# ArtFire.net
KiCad netlist of a schematic drawn in Altium Designer
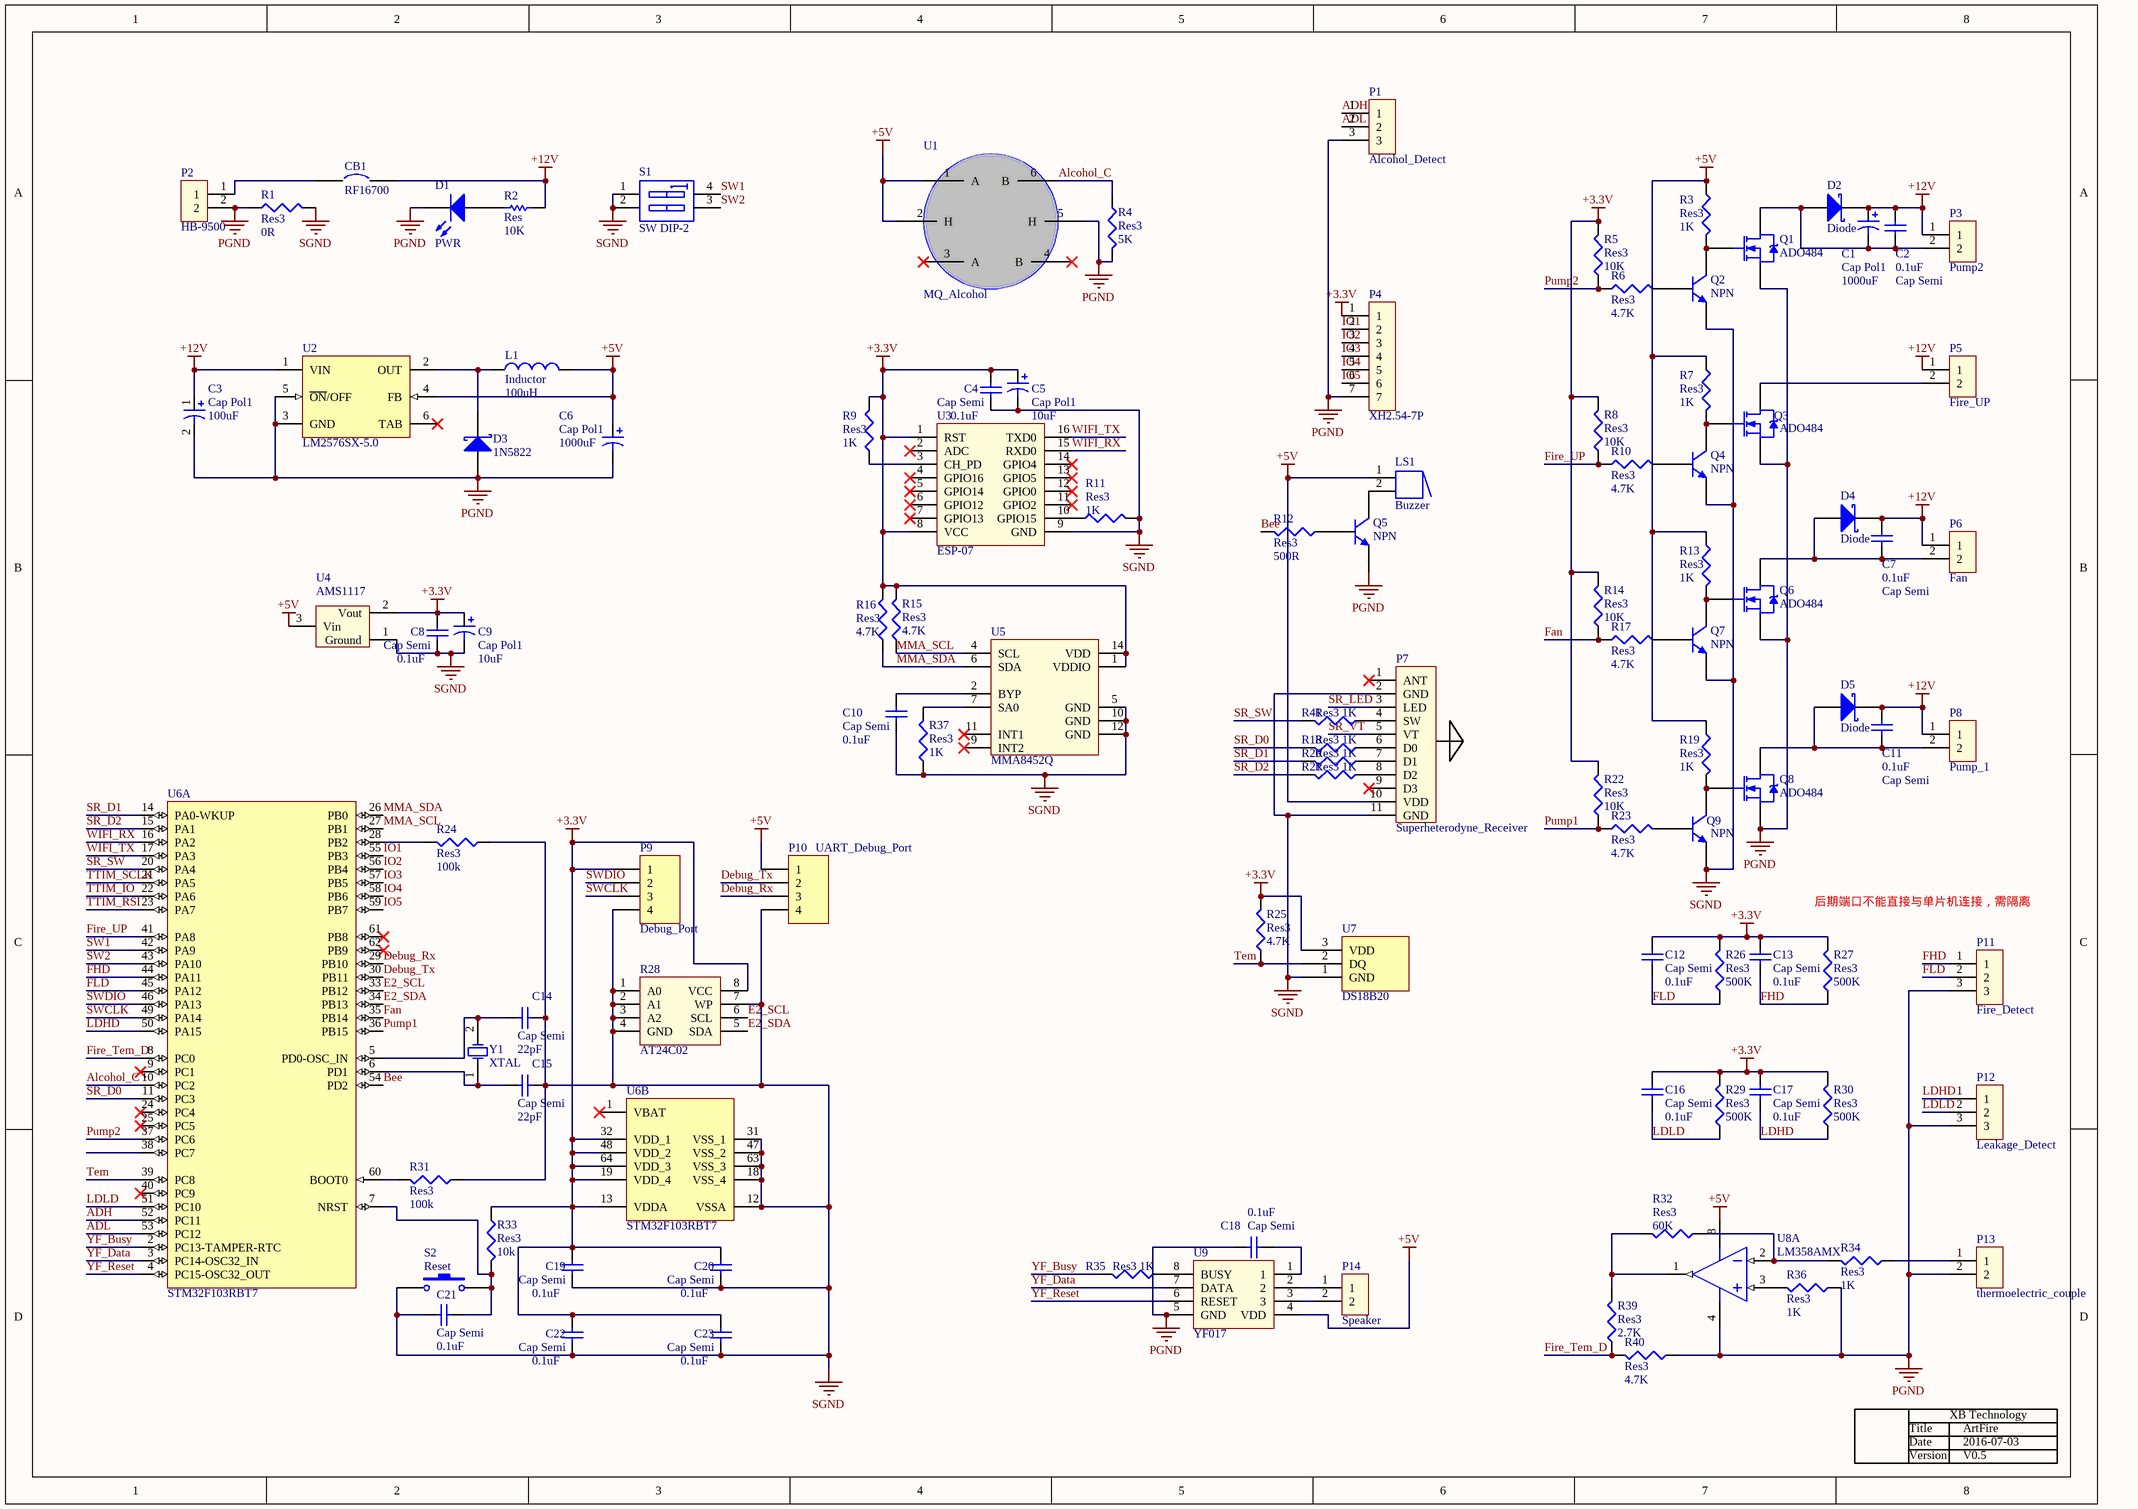
[diagram p0: ArtFire.SchDoc]

(export (version "E")
  (design (tool "Eeschema 10.0.6"))
  (components
    (comp (ref "C1")
      (value "Cap Pol1")
      (footprint "CAP_10*10MM")
      (description "Polarized Capacitor (Radial)")
      (fields (field (name "ALTIUM_VALUE") "1000uF"))
      (libsource (lib "Miscellaneous Devices") (part "Cap Pol1"))
    )
    (comp (ref "C2")
      (value "Cap Semi")
      (footprint "6-0805_N")
      (description "Capacitor (Semiconductor SIM Model)")
      (fields (field (name "ALTIUM_VALUE") "0.1uF"))
      (libsource (lib "Miscellaneous Devices") (part "Cap Semi"))
    )
    (comp (ref "C3")
      (value "Cap Pol1")
      (footprint "6032")
      (description "Polarized Capacitor (Radial)")
      (fields (field (name "ALTIUM_VALUE") "100uF"))
      (libsource (lib "") (part "Cap Pol1_1"))
    )
    (comp (ref "C4")
      (value "Cap Semi")
      (footprint "6-0805_N")
      (description "Capacitor (Semiconductor SIM Model)")
      (fields (field (name "ALTIUM_VALUE") "0.1uF"))
      (libsource (lib "Miscellaneous Devices") (part "Cap Semi"))
    )
    (comp (ref "C5")
      (value "Cap Pol1")
      (footprint "Cap_5*4mm")
      (description "Polarized Capacitor (Radial)")
      (fields (field (name "ALTIUM_VALUE") "10uF"))
      (libsource (lib "Miscellaneous Devices") (part "Cap Pol1"))
    )
    (comp (ref "C6")
      (value "Cap Pol1")
      (footprint "CAP_10*10MM")
      (description "Polarized Capacitor (Radial)")
      (fields (field (name "ALTIUM_VALUE") "1000uF"))
      (libsource (lib "Miscellaneous Devices") (part "Cap Pol1"))
    )
    (comp (ref "C7")
      (value "Cap Semi")
      (footprint "6-0805_N")
      (description "Capacitor (Semiconductor SIM Model)")
      (fields (field (name "ALTIUM_VALUE") "0.1uF"))
      (libsource (lib "Miscellaneous Devices") (part "Cap Semi"))
    )
    (comp (ref "C8")
      (value "Cap Semi")
      (footprint "6-0805_N")
      (description "Capacitor (Semiconductor SIM Model)")
      (fields (field (name "ALTIUM_VALUE") "0.1uF"))
      (libsource (lib "Miscellaneous Devices") (part "Cap Semi"))
    )
    (comp (ref "C9")
      (value "Cap Pol1")
      (footprint "Cap_5*4mm")
      (description "Polarized Capacitor (Radial)")
      (fields (field (name "ALTIUM_VALUE") "10uF"))
      (libsource (lib "Miscellaneous Devices") (part "Cap Pol1"))
    )
    (comp (ref "C10")
      (value "Cap Semi")
      (footprint "6-0805_N")
      (description "Capacitor (Semiconductor SIM Model)")
      (fields (field (name "ALTIUM_VALUE") "0.1uF"))
      (libsource (lib "Miscellaneous Devices") (part "Cap Semi"))
    )
    (comp (ref "C11")
      (value "Cap Semi")
      (footprint "6-0805_N")
      (description "Capacitor (Semiconductor SIM Model)")
      (fields (field (name "ALTIUM_VALUE") "0.1uF"))
      (libsource (lib "Miscellaneous Devices") (part "Cap Semi"))
    )
    (comp (ref "C12")
      (value "Cap Semi")
      (footprint "6-0805_N")
      (description "Capacitor (Semiconductor SIM Model)")
      (fields (field (name "ALTIUM_VALUE") "0.1uF"))
      (libsource (lib "Miscellaneous Devices") (part "Cap Semi"))
    )
    (comp (ref "C13")
      (value "Cap Semi")
      (footprint "6-0805_N")
      (description "Capacitor (Semiconductor SIM Model)")
      (fields (field (name "ALTIUM_VALUE") "0.1uF"))
      (libsource (lib "Miscellaneous Devices") (part "Cap Semi"))
    )
    (comp (ref "C14")
      (value "Cap Semi")
      (footprint "6-0805_N")
      (description "Capacitor (Semiconductor SIM Model)")
      (fields (field (name "ALTIUM_VALUE") "22pF"))
      (libsource (lib "Miscellaneous Devices") (part "Cap Semi"))
    )
    (comp (ref "C15")
      (value "Cap Semi")
      (footprint "6-0805_N")
      (description "Capacitor (Semiconductor SIM Model)")
      (fields (field (name "ALTIUM_VALUE") "22pF"))
      (libsource (lib "Miscellaneous Devices") (part "Cap Semi"))
    )
    (comp (ref "C16")
      (value "Cap Semi")
      (footprint "6-0805_N")
      (description "Capacitor (Semiconductor SIM Model)")
      (fields (field (name "ALTIUM_VALUE") "0.1uF"))
      (libsource (lib "Miscellaneous Devices") (part "Cap Semi"))
    )
    (comp (ref "C17")
      (value "Cap Semi")
      (footprint "6-0805_N")
      (description "Capacitor (Semiconductor SIM Model)")
      (fields (field (name "ALTIUM_VALUE") "0.1uF"))
      (libsource (lib "Miscellaneous Devices") (part "Cap Semi"))
    )
    (comp (ref "C18")
      (value "Cap Semi")
      (footprint "6-0805_N")
      (description "Capacitor (Semiconductor SIM Model)")
      (fields (field (name "ALTIUM_VALUE") "0.1uF"))
      (libsource (lib "Miscellaneous Devices") (part "Cap Semi"))
    )
    (comp (ref "C19")
      (value "Cap Semi")
      (footprint "6-0805_N")
      (description "Capacitor (Semiconductor SIM Model)")
      (fields (field (name "ALTIUM_VALUE") "0.1uF"))
      (libsource (lib "Miscellaneous Devices") (part "Cap Semi"))
    )
    (comp (ref "C20")
      (value "Cap Semi")
      (footprint "6-0805_N")
      (description "Capacitor (Semiconductor SIM Model)")
      (fields (field (name "ALTIUM_VALUE") "0.1uF"))
      (libsource (lib "Miscellaneous Devices") (part "Cap Semi"))
    )
    (comp (ref "C21")
      (value "Cap Semi")
      (footprint "6-0805_N")
      (description "Capacitor (Semiconductor SIM Model)")
      (fields (field (name "ALTIUM_VALUE") "0.1uF"))
      (libsource (lib "Miscellaneous Devices") (part "Cap Semi"))
    )
    (comp (ref "C22")
      (value "Cap Semi")
      (footprint "6-0805_N")
      (description "Capacitor (Semiconductor SIM Model)")
      (fields (field (name "ALTIUM_VALUE") "0.1uF"))
      (libsource (lib "Miscellaneous Devices") (part "Cap Semi"))
    )
    (comp (ref "C23")
      (value "Cap Semi")
      (footprint "6-0805_N")
      (description "Capacitor (Semiconductor SIM Model)")
      (fields (field (name "ALTIUM_VALUE") "0.1uF"))
      (libsource (lib "Miscellaneous Devices") (part "Cap Semi"))
    )
    (comp (ref "CB1")
      (value "RF16700")
      (footprint "SPST-2")
      (description "Circuit Breaker")
      (libsource (lib "Miscellaneous Devices") (part "Circuit Breaker"))
    )
    (comp (ref "D1")
      (value "PWR")
      (footprint "6-0805_N")
      (description "Typical INFRARED GaAs LED")
      (libsource (lib "Miscellaneous Devices") (part "LED0"))
    )
    (comp (ref "D2")
      (value "Diode")
      (footprint "US1M")
      (description "Silicon RF Schottky Diode for Mixer Applications in the VHF/UHF Range")
      (libsource (lib "Miscellaneous Devices") (part "Diode BAT17"))
    )
    (comp (ref "D3")
      (value "1N5822")
      (footprint "US1M")
      (description "Silicon RF Schottky Diode for Mixer Applications in the VHF/UHF Range")
      (libsource (lib "Miscellaneous Devices") (part "Diode BAT17"))
    )
    (comp (ref "D4")
      (value "Diode")
      (footprint "US1M")
      (description "Silicon RF Schottky Diode for Mixer Applications in the VHF/UHF Range")
      (libsource (lib "Miscellaneous Devices") (part "Diode BAT17"))
    )
    (comp (ref "D5")
      (value "Diode")
      (footprint "US1M")
      (description "Silicon RF Schottky Diode for Mixer Applications in the VHF/UHF Range")
      (libsource (lib "Miscellaneous Devices") (part "Diode BAT17"))
    )
    (comp (ref "L1")
      (value "Inductor")
      (footprint "CDRH127")
      (fields (field (name "ALTIUM_VALUE") "100uH"))
      (libsource (lib "Miscellaneous Devices") (part "Inductor"))
    )
    (comp (ref "LS1")
      (value "Buzzer")
      (footprint "BUZZER")
      (description "Magnetic Transducer Buzzer")
      (libsource (lib "Miscellaneous Devices") (part "Buzzer"))
    )
    (comp (ref "P1")
      (value "Alcohol_Detect")
      (footprint "XH2.54-3P")
      (libsource (lib "XH2.54") (part "XH2.54-3P"))
    )
    (comp (ref "P2")
      (value "HB-9500")
      (footprint "HB-9500")
      (description "High current connector")
      (libsource (lib "Simon'Library") (part "HB-9500"))
    )
    (comp (ref "P3") (value "Pump2") (footprint "CH3.96_2P") (libsource (lib "CH3.96") (part "CH3.96_2P")))
    (comp (ref "P4")
      (value "XH2.54-7P")
      (footprint "XH2.54-7P")
      (libsource (lib "XH2.54") (part "XH2.54-7P"))
    )
    (comp (ref "P5") (value "Fire_UP") (footprint "KF3.96_2P") (libsource (lib "KF3.96") (part "KF3.96")))
    (comp (ref "P6") (value "Fan") (footprint "XH2.54-2P") (libsource (lib "XH2.54") (part "XH2.54-2P")))
    (comp (ref "P7")
      (value "Superheterodyne_Receiver")
      (footprint "Sperheterodyne_Receiver")
      (libsource (lib "Simon'Library") (part "Superheterodyne_Receiver"))
    )
    (comp (ref "P8") (value "Pump_1") (footprint "CH3.96_2P") (libsource (lib "CH3.96") (part "CH3.96_2P")))
    (comp (ref "P9")
      (value "Debug_Port")
      (footprint "HDR1X4")
      (description "Header, 4-Pin")
      (libsource (lib "Miscellaneous Connectors") (part "Header 4"))
    )
    (comp (ref "P10")
      (value "UART_Debug_Port")
      (footprint "HDR1X4")
      (description "Header, 4-Pin")
      (libsource (lib "Miscellaneous Connectors") (part "Header 4"))
    )
    (comp (ref "P11")
      (value "Fire_Detect")
      (footprint "CH3.96_3P")
      (libsource (lib "CH3.96") (part "CH3.96_3P"))
    )
    (comp (ref "P12")
      (value "Leakage_Detect")
      (footprint "XH2.54-3P")
      (libsource (lib "XH2.54") (part "XH2.54-3P"))
    )
    (comp (ref "P13")
      (value "thermoelectric_couple")
      (footprint "KF7.62-2P")
      (libsource (lib "KF3.96") (part "KF3.96"))
    )
    (comp (ref "P14") (value "Speaker") (footprint "XH2.54-2P") (libsource (lib "XH2.54") (part "XH2.54-2P")))
    (comp (ref "Q1")
      (value "ADO484")
      (footprint "DPAK_AOD484")
      (description "N-Channel Power MOSFET")
      (libsource (lib "Miscellaneous Devices") (part "NMOS-2"))
    )
    (comp (ref "Q2")
      (value "NPN")
      (footprint "SOT-23_N")
      (description "NPN Bipolar Transistor")
      (libsource (lib "Miscellaneous Devices") (part "NPN"))
    )
    (comp (ref "Q3")
      (value "ADO484")
      (footprint "DPAK_AOD484")
      (description "N-Channel Power MOSFET")
      (libsource (lib "Miscellaneous Devices") (part "NMOS-2"))
    )
    (comp (ref "Q4")
      (value "NPN")
      (footprint "SOT-23_N")
      (description "NPN Bipolar Transistor")
      (libsource (lib "Miscellaneous Devices") (part "NPN"))
    )
    (comp (ref "Q5")
      (value "NPN")
      (footprint "SOT-23_N")
      (description "NPN Bipolar Transistor")
      (libsource (lib "Miscellaneous Devices") (part "NPN"))
    )
    (comp (ref "Q6")
      (value "ADO484")
      (footprint "DPAK_AOD484")
      (description "N-Channel Power MOSFET")
      (libsource (lib "Miscellaneous Devices") (part "NMOS-2"))
    )
    (comp (ref "Q7")
      (value "NPN")
      (footprint "SOT-23_N")
      (description "NPN Bipolar Transistor")
      (libsource (lib "Miscellaneous Devices") (part "NPN"))
    )
    (comp (ref "Q8")
      (value "ADO484")
      (footprint "DPAK_AOD484")
      (description "N-Channel Power MOSFET")
      (libsource (lib "Miscellaneous Devices") (part "NMOS-2"))
    )
    (comp (ref "Q9")
      (value "NPN")
      (footprint "SOT-23_N")
      (description "NPN Bipolar Transistor")
      (libsource (lib "Miscellaneous Devices") (part "NPN"))
    )
    (comp (ref "R1")
      (value "Res3")
      (footprint "6-0805_N")
      (description "Resistor")
      (fields (field (name "ALTIUM_VALUE") "0R"))
      (libsource (lib "Miscellaneous Devices") (part "Res3"))
    )
    (comp (ref "R2")
      (value "Res")
      (footprint "6-0805_N")
      (description "Resistor")
      (fields (field (name "ALTIUM_VALUE") "10K"))
      (libsource (lib "Miscellaneous Devices") (part "Res1"))
    )
    (comp (ref "R3")
      (value "Res3")
      (footprint "6-0805_N")
      (description "Resistor")
      (fields (field (name "ALTIUM_VALUE") "1K"))
      (libsource (lib "Miscellaneous Devices") (part "Res3"))
    )
    (comp (ref "R4")
      (value "Res3")
      (footprint "6-0805_N")
      (description "Resistor")
      (fields (field (name "ALTIUM_VALUE") "5K"))
      (libsource (lib "Miscellaneous Devices") (part "Res3"))
    )
    (comp (ref "R5")
      (value "Res3")
      (footprint "6-0805_N")
      (description "Resistor")
      (fields (field (name "ALTIUM_VALUE") "10K"))
      (libsource (lib "Miscellaneous Devices") (part "Res3"))
    )
    (comp (ref "R6")
      (value "Res3")
      (footprint "6-0805_N")
      (description "Resistor")
      (fields (field (name "ALTIUM_VALUE") "4.7K"))
      (libsource (lib "Miscellaneous Devices") (part "Res3"))
    )
    (comp (ref "R7")
      (value "Res3")
      (footprint "6-0805_N")
      (description "Resistor")
      (fields (field (name "ALTIUM_VALUE") "1K"))
      (libsource (lib "Miscellaneous Devices") (part "Res3"))
    )
    (comp (ref "R8")
      (value "Res3")
      (footprint "6-0805_N")
      (description "Resistor")
      (fields (field (name "ALTIUM_VALUE") "10K"))
      (libsource (lib "Miscellaneous Devices") (part "Res3"))
    )
    (comp (ref "R9")
      (value "Res3")
      (footprint "6-0805_N")
      (description "Resistor")
      (fields (field (name "ALTIUM_VALUE") "1K"))
      (libsource (lib "Miscellaneous Devices") (part "Res3"))
    )
    (comp (ref "R10")
      (value "Res3")
      (footprint "6-0805_N")
      (description "Resistor")
      (fields (field (name "ALTIUM_VALUE") "4.7K"))
      (libsource (lib "Miscellaneous Devices") (part "Res3"))
    )
    (comp (ref "R11")
      (value "Res3")
      (footprint "6-0805_N")
      (description "Resistor")
      (fields (field (name "ALTIUM_VALUE") "1K"))
      (libsource (lib "Miscellaneous Devices") (part "Res3"))
    )
    (comp (ref "R12")
      (value "Res3")
      (footprint "6-0805_N")
      (description "Resistor")
      (fields (field (name "ALTIUM_VALUE") "500R"))
      (libsource (lib "Miscellaneous Devices") (part "Res3"))
    )
    (comp (ref "R13")
      (value "Res3")
      (footprint "6-0805_N")
      (description "Resistor")
      (fields (field (name "ALTIUM_VALUE") "1K"))
      (libsource (lib "Miscellaneous Devices") (part "Res3"))
    )
    (comp (ref "R14")
      (value "Res3")
      (footprint "6-0805_N")
      (description "Resistor")
      (fields (field (name "ALTIUM_VALUE") "10K"))
      (libsource (lib "Miscellaneous Devices") (part "Res3"))
    )
    (comp (ref "R15")
      (value "Res3")
      (footprint "6-0805_N")
      (description "Resistor")
      (fields (field (name "ALTIUM_VALUE") "4.7K"))
      (libsource (lib "Miscellaneous Devices") (part "Res3"))
    )
    (comp (ref "R16")
      (value "Res3")
      (footprint "6-0805_N")
      (description "Resistor")
      (fields (field (name "ALTIUM_VALUE") "4.7K"))
      (libsource (lib "Miscellaneous Devices") (part "Res3"))
    )
    (comp (ref "R17")
      (value "Res3")
      (footprint "6-0805_N")
      (description "Resistor")
      (fields (field (name "ALTIUM_VALUE") "4.7K"))
      (libsource (lib "Miscellaneous Devices") (part "Res3"))
    )
    (comp (ref "R18")
      (value "Res3")
      (footprint "6-0805_N")
      (description "Resistor")
      (fields (field (name "ALTIUM_VALUE") "1K"))
      (libsource (lib "Miscellaneous Devices") (part "Res3"))
    )
    (comp (ref "R19")
      (value "Res3")
      (footprint "6-0805_N")
      (description "Resistor")
      (fields (field (name "ALTIUM_VALUE") "1K"))
      (libsource (lib "Miscellaneous Devices") (part "Res3"))
    )
    (comp (ref "R20")
      (value "Res3")
      (footprint "6-0805_N")
      (description "Resistor")
      (fields (field (name "ALTIUM_VALUE") "1K"))
      (libsource (lib "Miscellaneous Devices") (part "Res3"))
    )
    (comp (ref "R21")
      (value "Res3")
      (footprint "6-0805_N")
      (description "Resistor")
      (fields (field (name "ALTIUM_VALUE") "1K"))
      (libsource (lib "Miscellaneous Devices") (part "Res3"))
    )
    (comp (ref "R22")
      (value "Res3")
      (footprint "6-0805_N")
      (description "Resistor")
      (fields (field (name "ALTIUM_VALUE") "10K"))
      (libsource (lib "Miscellaneous Devices") (part "Res3"))
    )
    (comp (ref "R23")
      (value "Res3")
      (footprint "6-0805_N")
      (description "Resistor")
      (fields (field (name "ALTIUM_VALUE") "4.7K"))
      (libsource (lib "Miscellaneous Devices") (part "Res3"))
    )
    (comp (ref "R24")
      (value "Res3")
      (footprint "6-0805_N")
      (description "Resistor")
      (fields (field (name "ALTIUM_VALUE") "100k"))
      (libsource (lib "Miscellaneous Devices") (part "Res3"))
    )
    (comp (ref "R25")
      (value "Res3")
      (footprint "6-0805_N")
      (description "Resistor")
      (fields (field (name "ALTIUM_VALUE") "4.7K"))
      (libsource (lib "Miscellaneous Devices") (part "Res3"))
    )
    (comp (ref "R26")
      (value "Res3")
      (footprint "6-0805_N")
      (description "Resistor")
      (fields (field (name "ALTIUM_VALUE") "500K"))
      (libsource (lib "Miscellaneous Devices") (part "Res3"))
    )
    (comp (ref "R27")
      (value "Res3")
      (footprint "6-0805_N")
      (description "Resistor")
      (fields (field (name "ALTIUM_VALUE") "500K"))
      (libsource (lib "Miscellaneous Devices") (part "Res3"))
    )
    (comp (ref "R28")
      (value "AT24C02")
      (footprint "SOP8_TDA2822")
      (libsource (lib "Simon'Library") (part "AT24C02"))
    )
    (comp (ref "R29")
      (value "Res3")
      (footprint "6-0805_N")
      (description "Resistor")
      (fields (field (name "ALTIUM_VALUE") "500K"))
      (libsource (lib "Miscellaneous Devices") (part "Res3"))
    )
    (comp (ref "R30")
      (value "Res3")
      (footprint "6-0805_N")
      (description "Resistor")
      (fields (field (name "ALTIUM_VALUE") "500K"))
      (libsource (lib "Miscellaneous Devices") (part "Res3"))
    )
    (comp (ref "R31")
      (value "Res3")
      (footprint "6-0805_N")
      (description "Resistor")
      (fields (field (name "ALTIUM_VALUE") "100k"))
      (libsource (lib "Miscellaneous Devices") (part "Res3"))
    )
    (comp (ref "R32")
      (value "Res3")
      (footprint "6-0805_N")
      (description "Resistor")
      (fields (field (name "ALTIUM_VALUE") "60K"))
      (libsource (lib "Miscellaneous Devices") (part "Res3"))
    )
    (comp (ref "R33")
      (value "Res3")
      (footprint "6-0805_N")
      (description "Resistor")
      (fields (field (name "ALTIUM_VALUE") "10k"))
      (libsource (lib "Miscellaneous Devices") (part "Res3"))
    )
    (comp (ref "R34")
      (value "Res3")
      (footprint "6-0805_N")
      (description "Resistor")
      (fields (field (name "ALTIUM_VALUE") "1K"))
      (libsource (lib "Miscellaneous Devices") (part "Res3"))
    )
    (comp (ref "R35")
      (value "Res3")
      (footprint "6-0805_N")
      (description "Resistor")
      (fields (field (name "ALTIUM_VALUE") "1K"))
      (libsource (lib "Miscellaneous Devices") (part "Res3"))
    )
    (comp (ref "R36")
      (value "Res3")
      (footprint "6-0805_N")
      (description "Resistor")
      (fields (field (name "ALTIUM_VALUE") "1K"))
      (libsource (lib "Miscellaneous Devices") (part "Res3"))
    )
    (comp (ref "R37")
      (value "Res3")
      (footprint "6-0805_N")
      (description "Resistor")
      (fields (field (name "ALTIUM_VALUE") "1K"))
      (libsource (lib "Miscellaneous Devices") (part "Res3"))
    )
    (comp (ref "R39")
      (value "Res3")
      (footprint "6-0805_N")
      (description "Resistor")
      (fields (field (name "ALTIUM_VALUE") "2.7K"))
      (libsource (lib "Miscellaneous Devices") (part "Res3"))
    )
    (comp (ref "R40")
      (value "Res3")
      (footprint "6-0805_N")
      (description "Resistor")
      (fields (field (name "ALTIUM_VALUE") "4.7K"))
      (libsource (lib "Miscellaneous Devices") (part "Res3"))
    )
    (comp (ref "R41")
      (value "Res3")
      (footprint "6-0805_N")
      (description "Resistor")
      (fields (field (name "ALTIUM_VALUE") "1K"))
      (libsource (lib "Miscellaneous Devices") (part "Res3"))
    )
    (comp (ref "S1")
      (value "SW DIP-2")
      (footprint "DIP-4")
      (description "DIP Switch, 2 Position, SPST")
      (libsource (lib "Miscellaneous Devices") (part "SW DIP-2"))
    )
    (comp (ref "S2")
      (value "Reset")
      (footprint "SWP_PB_6.5mm")
      (description "Switch")
      (libsource (lib "Miscellaneous Devices") (part "SW-PB"))
    )
    (comp (ref "U1") (value "MQ_Alcohol") (footprint "MQ") (libsource (lib "Simon'Library") (part "MQ")))
    (comp (ref "U2")
      (value "LM2576SX-5.0")
      (footprint "TS5B_L")
      (description "SIMPLE SWITCHER® 3A Step-Down Voltage Regulator, 5-pin TO-263")
      (fields (field (name "MANUFACTURER") "National Semiconductor"))
      (libsource (lib "Altium Content Vault") (part "PM-REG-LM2575HVS-12"))
    )
    (comp (ref "U3")
      (value "ESP-07")
      (footprint "ESP-07_Wifi")
      (libsource (lib "Simon'Library") (part "ESP-07_Wifi"))
    )
    (comp (ref "U4")
      (value "AMS1117")
      (footprint "SOT223_N")
      (libsource (lib "Simon'Library") (part "AMS1117"))
    )
    (comp (ref "U5")
      (value "MMA8452Q")
      (footprint "QFN-16")
      (libsource (lib "Simon'Library") (part "MMA8452Q"))
    )
    (comp (ref "U6")
      (value "STM32F103RBT7")
      (footprint "LQFP64_L")
      (libsource (lib "Altium Content Vault") (part "MC-ARM-STM32F101-SQ64"))
    )
    (comp (ref "U7")
      (value "DS18B20")
      (footprint "TO-92A")
      (libsource (lib "Simon'Library") (part "DS18B20"))
    )
    (comp (ref "U8")
      (value "LM358AMX")
      (footprint "M08A_M")
      (description "Low Power Dual Operational Amplifier, 8-pin Narrow SOIC")
      (fields (field (name "MANUFACTURER") "National Semiconductor"))
      (libsource (lib "Altium Content Vault") (part "AMP-OPA-LM158-8"))
    )
    (comp (ref "U9") (value "YF017") (footprint "DIP-8") (libsource (lib "Simon'Library") (part "YF017")))
    (comp (ref "Y1")
      (value "XTAL")
      (footprint "XTAL")
      (description "Crystal Oscillator")
      (libsource (lib "Miscellaneous Devices") (part "XTAL"))
    )
  )
  (nets
    (net (code "1") (name "+3.3V") (class "Default")
      (node (ref "C12") (pin "2") (pinfunction "2_2") (pintype "passive"))
      (node (ref "C13") (pin "2") (pinfunction "2_2") (pintype "passive"))
      (node (ref "C16") (pin "2") (pinfunction "2_2") (pintype "passive"))
      (node (ref "C17") (pin "2") (pinfunction "2_2") (pintype "passive"))
      (node (ref "C19") (pin "1") (pinfunction "1_1") (pintype "passive"))
      (node (ref "C20") (pin "1") (pinfunction "1_1") (pintype "passive"))
      (node (ref "C22") (pin "1") (pinfunction "1_1") (pintype "passive"))
      (node (ref "C23") (pin "1") (pinfunction "1_1") (pintype "passive"))
      (node (ref "C4") (pin "1") (pinfunction "1_1") (pintype "passive"))
      (node (ref "C5") (pin "1") (pinfunction "1_1") (pintype "passive"))
      (node (ref "C8") (pin "1") (pinfunction "1_1") (pintype "passive"))
      (node (ref "C9") (pin "1") (pinfunction "1_1") (pintype "passive"))
      (node (ref "P4") (pin "1") (pinfunction "1_1") (pintype "passive"))
      (node (ref "P9") (pin "1") (pinfunction "1_1") (pintype "passive"))
      (node (ref "R14") (pin "2") (pinfunction "2_2") (pintype "passive"))
      (node (ref "R15") (pin "2") (pinfunction "2_2") (pintype "passive"))
      (node (ref "R16") (pin "2") (pinfunction "2_2") (pintype "passive"))
      (node (ref "R22") (pin "2") (pinfunction "2_2") (pintype "passive"))
      (node (ref "R25") (pin "2") (pinfunction "2_2") (pintype "passive"))
      (node (ref "R26") (pin "2") (pinfunction "2_2") (pintype "passive"))
      (node (ref "R27") (pin "2") (pinfunction "2_2") (pintype "passive"))
      (node (ref "R28") (pin "8") (pinfunction "VCC_8") (pintype "passive"))
      (node (ref "R29") (pin "2") (pinfunction "2_2") (pintype "passive"))
      (node (ref "R30") (pin "2") (pinfunction "2_2") (pintype "passive"))
      (node (ref "R33") (pin "1") (pinfunction "1_1") (pintype "passive"))
      (node (ref "R5") (pin "2") (pinfunction "2_2") (pintype "passive"))
      (node (ref "R8") (pin "2") (pinfunction "2_2") (pintype "passive"))
      (node (ref "R9") (pin "2") (pinfunction "2_2") (pintype "passive"))
      (node (ref "U3") (pin "1") (pinfunction "RST_1") (pintype "passive"))
      (node (ref "U3") (pin "8") (pinfunction "VCC_8") (pintype "passive"))
      (node (ref "U4") (pin "2") (pinfunction "Vout_2") (pintype "passive"))
      (node (ref "U5") (pin "1") (pinfunction "VDDIO_1") (pintype "passive"))
      (node (ref "U5") (pin "14") (pinfunction "VDD_14") (pintype "passive"))
      (node (ref "U6") (pin "13") (pinfunction "VDDA_13") (pintype "power_in"))
      (node (ref "U6") (pin "19") (pinfunction "VDD_4_19") (pintype "power_in"))
      (node (ref "U6") (pin "32") (pinfunction "VDD_1_32") (pintype "power_in"))
      (node (ref "U6") (pin "48") (pinfunction "VDD_2_48") (pintype "power_in"))
      (node (ref "U6") (pin "64") (pinfunction "VDD_3_64") (pintype "power_in"))
      (node (ref "U7") (pin "3") (pinfunction "VDD_3") (pintype "passive"))
    )
    (net (code "2") (name "+5V") (class "Default")
      (node (ref "C6") (pin "1") (pinfunction "1_1") (pintype "passive"))
      (node (ref "L1") (pin "2") (pinfunction "2_2") (pintype "passive"))
      (node (ref "LS1") (pin "1") (pinfunction "1_1") (pintype "passive"))
      (node (ref "P10") (pin "1") (pinfunction "1_1") (pintype "passive"))
      (node (ref "P7") (pin "10") (pinfunction "VDD_10") (pintype "passive"))
      (node (ref "R13") (pin "1") (pinfunction "1_1") (pintype "passive"))
      (node (ref "R19") (pin "1") (pinfunction "1_1") (pintype "passive"))
      (node (ref "R3") (pin "1") (pinfunction "1_1") (pintype "passive"))
      (node (ref "R7") (pin "1") (pinfunction "1_1") (pintype "passive"))
      (node (ref "U1") (pin "1") (pinfunction "A_1") (pintype "passive"))
      (node (ref "U1") (pin "2") (pinfunction "H_2") (pintype "passive"))
      (node (ref "U2") (pin "4") (pinfunction "FB_4") (pintype "input"))
      (node (ref "U4") (pin "3") (pinfunction "Vin_3") (pintype "passive"))
      (node (ref "U8") (pin "8") (pinfunction "V+_8") (pintype "power_in"))
      (node (ref "U9") (pin "4") (pinfunction "VDD_4") (pintype "passive"))
    )
    (net (code "3") (name "+12V") (class "Default")
      (node (ref "C1") (pin "1") (pinfunction "1_1") (pintype "passive"))
      (node (ref "C11") (pin "1") (pinfunction "1_1") (pintype "passive"))
      (node (ref "C2") (pin "1") (pinfunction "1_1") (pintype "passive"))
      (node (ref "C3") (pin "1") (pinfunction "1_1") (pintype "passive"))
      (node (ref "C7") (pin "1") (pinfunction "1_1") (pintype "passive"))
      (node (ref "CB1") (pin "2") (pinfunction "2_2") (pintype "passive"))
      (node (ref "D2") (pin "2") (pinfunction "K_2") (pintype "passive"))
      (node (ref "D4") (pin "2") (pinfunction "K_2") (pintype "passive"))
      (node (ref "D5") (pin "2") (pinfunction "K_2") (pintype "passive"))
      (node (ref "P3") (pin "1") (pinfunction "1_1") (pintype "passive"))
      (node (ref "P5") (pin "1") (pinfunction "1_1") (pintype "passive"))
      (node (ref "P6") (pin "1") (pinfunction "1_1") (pintype "passive"))
      (node (ref "P8") (pin "1") (pinfunction "1_1") (pintype "passive"))
      (node (ref "R2") (pin "2") (pinfunction "2_2") (pintype "passive"))
      (node (ref "U2") (pin "1") (pinfunction "VIN_1") (pintype "power_in"))
    )
    (net (code "4") (name "/ADH") (class "Default")
      (node (ref "P1") (pin "1") (pinfunction "1_1") (pintype "passive"))
      (node (ref "U6") (pin "52") (pinfunction "PC11_52") (pintype "bidirectional"))
    )
    (net (code "5") (name "/ADL") (class "Default")
      (node (ref "P1") (pin "2") (pinfunction "2_2") (pintype "passive"))
      (node (ref "U6") (pin "53") (pinfunction "PC12_53") (pintype "bidirectional"))
    )
    (net (code "6") (name "/Alcohol_C") (class "Default")
      (node (ref "R4") (pin "1") (pinfunction "1_1") (pintype "passive"))
      (node (ref "U1") (pin "6") (pinfunction "B_6") (pintype "passive"))
      (node (ref "U6") (pin "10") (pinfunction "PC2_10") (pintype "bidirectional"))
    )
    (net (code "7") (name "/Bee") (class "Default")
      (node (ref "R12") (pin "2") (pinfunction "2_2") (pintype "passive"))
      (node (ref "U6") (pin "54") (pinfunction "PD2_54") (pintype "bidirectional"))
    )
    (net (code "8") (name "/Debug_Rx") (class "Default")
      (node (ref "P10") (pin "3") (pinfunction "3_3") (pintype "passive"))
      (node (ref "U6") (pin "29") (pinfunction "PB10_29") (pintype "bidirectional"))
    )
    (net (code "9") (name "/Debug_Tx") (class "Default")
      (node (ref "P10") (pin "2") (pinfunction "2_2") (pintype "passive"))
      (node (ref "U6") (pin "30") (pinfunction "PB11_30") (pintype "bidirectional"))
    )
    (net (code "10") (name "/E2_SCL") (class "Default")
      (node (ref "R28") (pin "6") (pinfunction "SCL_6") (pintype "passive"))
      (node (ref "U6") (pin "33") (pinfunction "PB12_33") (pintype "bidirectional"))
    )
    (net (code "11") (name "/E2_SDA") (class "Default")
      (node (ref "R28") (pin "5") (pinfunction "SDA_5") (pintype "passive"))
      (node (ref "U6") (pin "34") (pinfunction "PB13_34") (pintype "bidirectional"))
    )
    (net (code "12") (name "/FHD") (class "Default")
      (node (ref "C13") (pin "1") (pinfunction "1_1") (pintype "passive"))
      (node (ref "P11") (pin "1") (pinfunction "1_1") (pintype "passive"))
      (node (ref "R27") (pin "1") (pinfunction "1_1") (pintype "passive"))
      (node (ref "U6") (pin "44") (pinfunction "PA11_44") (pintype "bidirectional"))
    )
    (net (code "13") (name "/FLD") (class "Default")
      (node (ref "C12") (pin "1") (pinfunction "1_1") (pintype "passive"))
      (node (ref "P11") (pin "2") (pinfunction "2_2") (pintype "passive"))
      (node (ref "R26") (pin "1") (pinfunction "1_1") (pintype "passive"))
      (node (ref "U6") (pin "45") (pinfunction "PA12_45") (pintype "bidirectional"))
    )
    (net (code "14") (name "/Fan") (class "Default")
      (node (ref "R14") (pin "1") (pinfunction "1_1") (pintype "passive"))
      (node (ref "R17") (pin "1") (pinfunction "1_1") (pintype "passive"))
      (node (ref "U6") (pin "35") (pinfunction "PB14_35") (pintype "bidirectional"))
    )
    (net (code "15") (name "/Fire_Tem_D") (class "Default")
      (node (ref "R39") (pin "1") (pinfunction "1_1") (pintype "passive"))
      (node (ref "R40") (pin "2") (pinfunction "2_2") (pintype "passive"))
      (node (ref "U6") (pin "8") (pinfunction "PC0_8") (pintype "bidirectional"))
    )
    (net (code "16") (name "/Fire_UP") (class "Default")
      (node (ref "R10") (pin "1") (pinfunction "1_1") (pintype "passive"))
      (node (ref "R8") (pin "1") (pinfunction "1_1") (pintype "passive"))
      (node (ref "U6") (pin "41") (pinfunction "PA8_41") (pintype "bidirectional"))
    )
    (net (code "17") (name "/IO1") (class "Default")
      (node (ref "P4") (pin "2") (pinfunction "2_2") (pintype "passive"))
      (node (ref "U6") (pin "55") (pinfunction "PB3_55") (pintype "bidirectional"))
    )
    (net (code "18") (name "/IO2") (class "Default")
      (node (ref "P4") (pin "3") (pinfunction "3_3") (pintype "passive"))
      (node (ref "U6") (pin "56") (pinfunction "PB4_56") (pintype "bidirectional"))
    )
    (net (code "19") (name "/IO3") (class "Default")
      (node (ref "P4") (pin "4") (pinfunction "4_4") (pintype "passive"))
      (node (ref "U6") (pin "57") (pinfunction "PB5_57") (pintype "bidirectional"))
    )
    (net (code "20") (name "/IO4") (class "Default")
      (node (ref "P4") (pin "5") (pinfunction "5_5") (pintype "passive"))
      (node (ref "U6") (pin "58") (pinfunction "PB6_58") (pintype "bidirectional"))
    )
    (net (code "21") (name "/IO5") (class "Default")
      (node (ref "P4") (pin "6") (pinfunction "6_6") (pintype "passive"))
      (node (ref "U6") (pin "59") (pinfunction "PB7_59") (pintype "bidirectional"))
    )
    (net (code "22") (name "/LDHD") (class "Default")
      (node (ref "C17") (pin "1") (pinfunction "1_1") (pintype "passive"))
      (node (ref "P12") (pin "1") (pinfunction "1_1") (pintype "passive"))
      (node (ref "R30") (pin "1") (pinfunction "1_1") (pintype "passive"))
      (node (ref "U6") (pin "50") (pinfunction "PA15_50") (pintype "bidirectional"))
    )
    (net (code "23") (name "/LDLD") (class "Default")
      (node (ref "C16") (pin "1") (pinfunction "1_1") (pintype "passive"))
      (node (ref "P12") (pin "2") (pinfunction "2_2") (pintype "passive"))
      (node (ref "R29") (pin "1") (pinfunction "1_1") (pintype "passive"))
      (node (ref "U6") (pin "51") (pinfunction "PC10_51") (pintype "bidirectional"))
    )
    (net (code "24") (name "/MMA_SCL") (class "Default")
      (node (ref "R15") (pin "1") (pinfunction "1_1") (pintype "passive"))
      (node (ref "U5") (pin "4") (pinfunction "SCL_4") (pintype "passive"))
      (node (ref "U6") (pin "27") (pinfunction "PB1_27") (pintype "bidirectional"))
    )
    (net (code "25") (name "/MMA_SDA") (class "Default")
      (node (ref "R16") (pin "1") (pinfunction "1_1") (pintype "passive"))
      (node (ref "U5") (pin "6") (pinfunction "SDA_6") (pintype "passive"))
      (node (ref "U6") (pin "26") (pinfunction "PB0_26") (pintype "bidirectional"))
    )
    (net (code "26") (name "/Pump1") (class "Default")
      (node (ref "R22") (pin "1") (pinfunction "1_1") (pintype "passive"))
      (node (ref "R23") (pin "1") (pinfunction "1_1") (pintype "passive"))
      (node (ref "U6") (pin "36") (pinfunction "PB15_36") (pintype "bidirectional"))
    )
    (net (code "27") (name "/Pump2") (class "Default")
      (node (ref "R5") (pin "1") (pinfunction "1_1") (pintype "passive"))
      (node (ref "R6") (pin "1") (pinfunction "1_1") (pintype "passive"))
      (node (ref "U6") (pin "37") (pinfunction "PC6_37") (pintype "bidirectional"))
    )
    (net (code "28") (name "/SR_D0") (class "Default")
      (node (ref "R18") (pin "2") (pinfunction "2_2") (pintype "passive"))
      (node (ref "U6") (pin "11") (pinfunction "PC3_11") (pintype "bidirectional"))
    )
    (net (code "29") (name "/SR_D1") (class "Default")
      (node (ref "R20") (pin "2") (pinfunction "2_2") (pintype "passive"))
      (node (ref "U6") (pin "14") (pinfunction "PA0-WKUP_14") (pintype "bidirectional"))
    )
    (net (code "30") (name "/SR_D2") (class "Default")
      (node (ref "R21") (pin "2") (pinfunction "2_2") (pintype "passive"))
      (node (ref "U6") (pin "15") (pinfunction "PA1_15") (pintype "bidirectional"))
    )
    (net (code "31") (name "/SR_LED") (class "Default")
      (node (ref "P7") (pin "3") (pinfunction "LED_3") (pintype "passive"))
    )
    (net (code "32") (name "/SR_SW") (class "Default")
      (node (ref "R41") (pin "2") (pinfunction "2_2") (pintype "passive"))
      (node (ref "U6") (pin "20") (pinfunction "PA4_20") (pintype "bidirectional"))
    )
    (net (code "33") (name "/SR_VT") (class "Default")
      (node (ref "P7") (pin "5") (pinfunction "VT_5") (pintype "passive"))
    )
    (net (code "34") (name "/SW1") (class "Default")
      (node (ref "S1") (pin "4") (pinfunction "B1_4") (pintype "passive"))
      (node (ref "U6") (pin "42") (pinfunction "PA9_42") (pintype "bidirectional"))
    )
    (net (code "35") (name "/SW2") (class "Default")
      (node (ref "S1") (pin "3") (pinfunction "B2_3") (pintype "passive"))
      (node (ref "U6") (pin "43") (pinfunction "PA10_43") (pintype "bidirectional"))
    )
    (net (code "36") (name "/SWCLK") (class "Default")
      (node (ref "P9") (pin "3") (pinfunction "3_3") (pintype "passive"))
      (node (ref "U6") (pin "49") (pinfunction "PA14_49") (pintype "bidirectional"))
    )
    (net (code "37") (name "/SWDIO") (class "Default")
      (node (ref "P9") (pin "2") (pinfunction "2_2") (pintype "passive"))
      (node (ref "U6") (pin "46") (pinfunction "PA13_46") (pintype "bidirectional"))
    )
    (net (code "38") (name "/TTIM_IO") (class "Default")
      (node (ref "U6") (pin "22") (pinfunction "PA6_22") (pintype "bidirectional"))
    )
    (net (code "39") (name "/TTIM_RSI") (class "Default")
      (node (ref "U6") (pin "23") (pinfunction "PA7_23") (pintype "bidirectional"))
    )
    (net (code "40") (name "/TTIM_SCLK") (class "Default")
      (node (ref "U6") (pin "21") (pinfunction "PA5_21") (pintype "bidirectional"))
    )
    (net (code "41") (name "/Tem") (class "Default")
      (node (ref "R25") (pin "1") (pinfunction "1_1") (pintype "passive"))
      (node (ref "U6") (pin "39") (pinfunction "PC8_39") (pintype "bidirectional"))
      (node (ref "U7") (pin "2") (pinfunction "DQ_2") (pintype "passive"))
    )
    (net (code "42") (name "/WIFI_RX") (class "Default")
      (node (ref "U3") (pin "15") (pinfunction "RXD0_15") (pintype "passive"))
      (node (ref "U6") (pin "16") (pinfunction "PA2_16") (pintype "bidirectional"))
    )
    (net (code "43") (name "/WIFI_TX") (class "Default")
      (node (ref "U3") (pin "16") (pinfunction "TXD0_16") (pintype "passive"))
      (node (ref "U6") (pin "17") (pinfunction "PA3_17") (pintype "bidirectional"))
    )
    (net (code "44") (name "/YF_Busy") (class "Default")
      (node (ref "R35") (pin "2") (pinfunction "2_2") (pintype "passive"))
      (node (ref "U6") (pin "2") (pinfunction "PC13-TAMPER-RTC_2") (pintype "bidirectional"))
    )
    (net (code "45") (name "/YF_Data") (class "Default")
      (node (ref "U6") (pin "3") (pinfunction "PC14-OSC32_IN_3") (pintype "bidirectional"))
      (node (ref "U9") (pin "7") (pinfunction "DATA_7") (pintype "passive"))
    )
    (net (code "46") (name "/YF_Reset") (class "Default")
      (node (ref "U6") (pin "4") (pinfunction "PC15-OSC32_OUT_4") (pintype "bidirectional"))
      (node (ref "U9") (pin "6") (pinfunction "RESET_6") (pintype "passive"))
    )
    (net (code "47") (name "Net-(C18-Pad2)") (class "Default")
      (node (ref "C18") (pin "2") (pinfunction "2_2") (pintype "passive"))
      (node (ref "U9") (pin "1") (pinfunction "1_1") (pintype "passive"))
    )
    (net (code "48") (name "Net-(CB1-Pad1)") (class "Default")
      (node (ref "CB1") (pin "1") (pinfunction "1_1") (pintype "passive"))
      (node (ref "P2") (pin "1") (pinfunction "1_1") (pintype "passive"))
    )
    (net (code "49") (name "Net-(D1-A)") (class "Default")
      (node (ref "D1") (pin "1") (pinfunction "A_1") (pintype "passive"))
      (node (ref "R2") (pin "1") (pinfunction "1_1") (pintype "passive"))
    )
    (net (code "50") (name "Net-(D2-A)") (class "Default")
      (node (ref "C1") (pin "2") (pinfunction "2_2") (pintype "passive"))
      (node (ref "C2") (pin "2") (pinfunction "2_2") (pintype "passive"))
      (node (ref "D2") (pin "1") (pinfunction "A_1") (pintype "passive"))
      (node (ref "P3") (pin "2") (pinfunction "2_2") (pintype "passive"))
      (node (ref "Q1") (pin "2") (pinfunction "D_2") (pintype "passive"))
    )
    (net (code "51") (name "Net-(D3-K)") (class "Default")
      (node (ref "D3") (pin "2") (pinfunction "K_2") (pintype "passive"))
      (node (ref "L1") (pin "1") (pinfunction "1_1") (pintype "passive"))
      (node (ref "U2") (pin "2") (pinfunction "OUT_2") (pintype "power_in"))
    )
    (net (code "52") (name "Net-(D4-A)") (class "Default")
      (node (ref "C7") (pin "2") (pinfunction "2_2") (pintype "passive"))
      (node (ref "D4") (pin "1") (pinfunction "A_1") (pintype "passive"))
      (node (ref "P6") (pin "2") (pinfunction "2_2") (pintype "passive"))
      (node (ref "Q6") (pin "2") (pinfunction "D_2") (pintype "passive"))
    )
    (net (code "53") (name "Net-(D5-A)") (class "Default")
      (node (ref "C11") (pin "2") (pinfunction "2_2") (pintype "passive"))
      (node (ref "D5") (pin "1") (pinfunction "A_1") (pintype "passive"))
      (node (ref "P8") (pin "2") (pinfunction "2_2") (pintype "passive"))
      (node (ref "Q8") (pin "2") (pinfunction "D_2") (pintype "passive"))
    )
    (net (code "54") (name "Net-(P7-D0)") (class "Default")
      (node (ref "P7") (pin "6") (pinfunction "D0_6") (pintype "passive"))
      (node (ref "R18") (pin "1") (pinfunction "1_1") (pintype "passive"))
    )
    (net (code "55") (name "Net-(P7-D1)") (class "Default")
      (node (ref "P7") (pin "7") (pinfunction "D1_7") (pintype "passive"))
      (node (ref "R20") (pin "1") (pinfunction "1_1") (pintype "passive"))
    )
    (net (code "56") (name "Net-(P7-D2)") (class "Default")
      (node (ref "P7") (pin "8") (pinfunction "D2_8") (pintype "passive"))
      (node (ref "R21") (pin "1") (pinfunction "1_1") (pintype "passive"))
    )
    (net (code "57") (name "Net-(P7-SW)") (class "Default")
      (node (ref "P7") (pin "4") (pinfunction "SW_4") (pintype "passive"))
      (node (ref "R41") (pin "1") (pinfunction "1_1") (pintype "passive"))
    )
    (net (code "58") (name "Net-(P13-Pad1)") (class "Default")
      (node (ref "P13") (pin "1") (pinfunction "1_1") (pintype "passive"))
      (node (ref "R34") (pin "1") (pinfunction "1_1") (pintype "passive"))
    )
    (net (code "59") (name "Net-(P14-Pad1)") (class "Default")
      (node (ref "P14") (pin "1") (pinfunction "1_1") (pintype "passive"))
      (node (ref "U9") (pin "2") (pinfunction "2_2") (pintype "passive"))
    )
    (net (code "60") (name "Net-(P14-Pad2)") (class "Default")
      (node (ref "P14") (pin "2") (pinfunction "2_2") (pintype "passive"))
      (node (ref "U9") (pin "3") (pinfunction "3_3") (pintype "passive"))
    )
    (net (code "61") (name "Net-(Q1-G)") (class "Default")
      (node (ref "Q1") (pin "1") (pinfunction "G_1") (pintype "passive"))
      (node (ref "Q2") (pin "3") (pinfunction "C_3") (pintype "passive"))
      (node (ref "R3") (pin "2") (pinfunction "2_2") (pintype "passive"))
    )
    (net (code "62") (name "Net-(Q2-B)") (class "Default")
      (node (ref "Q2") (pin "1") (pinfunction "B_1") (pintype "passive"))
      (node (ref "R6") (pin "2") (pinfunction "2_2") (pintype "passive"))
    )
    (net (code "63") (name "Net-(Q3-D)") (class "Default")
      (node (ref "P5") (pin "2") (pinfunction "2_2") (pintype "passive"))
      (node (ref "Q3") (pin "2") (pinfunction "D_2") (pintype "passive"))
    )
    (net (code "64") (name "Net-(Q3-G)") (class "Default")
      (node (ref "Q3") (pin "1") (pinfunction "G_1") (pintype "passive"))
      (node (ref "Q4") (pin "3") (pinfunction "C_3") (pintype "passive"))
      (node (ref "R7") (pin "2") (pinfunction "2_2") (pintype "passive"))
    )
    (net (code "65") (name "Net-(Q4-B)") (class "Default")
      (node (ref "Q4") (pin "1") (pinfunction "B_1") (pintype "passive"))
      (node (ref "R10") (pin "2") (pinfunction "2_2") (pintype "passive"))
    )
    (net (code "66") (name "Net-(Q5-B)") (class "Default")
      (node (ref "Q5") (pin "1") (pinfunction "B_1") (pintype "passive"))
      (node (ref "R12") (pin "1") (pinfunction "1_1") (pintype "passive"))
    )
    (net (code "67") (name "Net-(Q5-C)") (class "Default")
      (node (ref "LS1") (pin "2") (pinfunction "2_2") (pintype "passive"))
      (node (ref "Q5") (pin "3") (pinfunction "C_3") (pintype "passive"))
    )
    (net (code "68") (name "Net-(Q6-G)") (class "Default")
      (node (ref "Q6") (pin "1") (pinfunction "G_1") (pintype "passive"))
      (node (ref "Q7") (pin "3") (pinfunction "C_3") (pintype "passive"))
      (node (ref "R13") (pin "2") (pinfunction "2_2") (pintype "passive"))
    )
    (net (code "69") (name "Net-(Q7-B)") (class "Default")
      (node (ref "Q7") (pin "1") (pinfunction "B_1") (pintype "passive"))
      (node (ref "R17") (pin "2") (pinfunction "2_2") (pintype "passive"))
    )
    (net (code "70") (name "Net-(Q8-G)") (class "Default")
      (node (ref "Q8") (pin "1") (pinfunction "G_1") (pintype "passive"))
      (node (ref "Q9") (pin "3") (pinfunction "C_3") (pintype "passive"))
      (node (ref "R19") (pin "2") (pinfunction "2_2") (pintype "passive"))
    )
    (net (code "71") (name "Net-(Q9-B)") (class "Default")
      (node (ref "Q9") (pin "1") (pinfunction "B_1") (pintype "passive"))
      (node (ref "R23") (pin "2") (pinfunction "2_2") (pintype "passive"))
    )
    (net (code "72") (name "Net-(U3-CH_PD)") (class "Default")
      (node (ref "R9") (pin "1") (pinfunction "1_1") (pintype "passive"))
      (node (ref "U3") (pin "3") (pinfunction "CH_PD_3") (pintype "passive"))
    )
    (net (code "73") (name "Net-(U3-GPIO15)") (class "Default")
      (node (ref "R11") (pin "1") (pinfunction "1_1") (pintype "passive"))
      (node (ref "U3") (pin "10") (pinfunction "GPIO15_10") (pintype "passive"))
    )
    (net (code "74") (name "Net-(U5-BYP)") (class "Default")
      (node (ref "C10") (pin "2") (pinfunction "2_2") (pintype "passive"))
      (node (ref "U5") (pin "2") (pinfunction "BYP_2") (pintype "passive"))
    )
    (net (code "75") (name "Net-(U5-SA0)") (class "Default")
      (node (ref "R37") (pin "2") (pinfunction "2_2") (pintype "passive"))
      (node (ref "U5") (pin "7") (pinfunction "SA0_7") (pintype "passive"))
    )
    (net (code "76") (name "Net-(U6A-BOOT0)") (class "Default")
      (node (ref "R31") (pin "2") (pinfunction "2_2") (pintype "passive"))
      (node (ref "U6") (pin "60") (pinfunction "BOOT0_60") (pintype "input"))
    )
    (net (code "77") (name "Net-(U6A-NRST)") (class "Default")
      (node (ref "C21") (pin "2") (pinfunction "2_2") (pintype "passive"))
      (node (ref "R33") (pin "2") (pinfunction "2_2") (pintype "passive"))
      (node (ref "S2") (pin "2") (pinfunction "2_2") (pintype "passive"))
      (node (ref "U6") (pin "7") (pinfunction "NRST_7") (pintype "bidirectional"))
    )
    (net (code "78") (name "Net-(U6A-PB2)") (class "Default")
      (node (ref "R24") (pin "2") (pinfunction "2_2") (pintype "passive"))
      (node (ref "U6") (pin "28") (pinfunction "PB2_28") (pintype "bidirectional"))
    )
    (net (code "79") (name "Net-(U6A-PD0-OSC_IN)") (class "Default")
      (node (ref "C14") (pin "1") (pinfunction "1_1") (pintype "passive"))
      (node (ref "U6") (pin "5") (pinfunction "PD0-OSC_IN_5") (pintype "bidirectional"))
      (node (ref "Y1") (pin "2") (pinfunction "OSC2_2") (pintype "passive"))
    )
    (net (code "80") (name "Net-(U6A-PD1)") (class "Default")
      (node (ref "C15") (pin "1") (pinfunction "1_1") (pintype "passive"))
      (node (ref "U6") (pin "6") (pinfunction "PD1_6") (pintype "bidirectional"))
      (node (ref "Y1") (pin "1") (pinfunction "OSC1_1") (pintype "passive"))
    )
    (net (code "81") (name "Net-(U8A-INA+)") (class "Default")
      (node (ref "R36") (pin "2") (pinfunction "2_2") (pintype "passive"))
      (node (ref "U8") (pin "3") (pinfunction "INA+_3") (pintype "input"))
    )
    (net (code "82") (name "Net-(U8A-INA-)") (class "Default")
      (node (ref "R32") (pin "1") (pinfunction "1_1") (pintype "passive"))
      (node (ref "R34") (pin "2") (pinfunction "2_2") (pintype "passive"))
      (node (ref "U8") (pin "2") (pinfunction "INA-_2") (pintype "input"))
    )
    (net (code "83") (name "Net-(U8A-OUTA)") (class "Default")
      (node (ref "R32") (pin "2") (pinfunction "2_2") (pintype "passive"))
      (node (ref "R39") (pin "2") (pinfunction "2_2") (pintype "passive"))
      (node (ref "U8") (pin "1") (pinfunction "OUTA_1") (pintype "output"))
    )
    (net (code "84") (name "Net-(U9-BUSY)") (class "Default")
      (node (ref "R35") (pin "1") (pinfunction "1_1") (pintype "passive"))
      (node (ref "U9") (pin "8") (pinfunction "BUSY_8") (pintype "passive"))
    )
    (net (code "85") (name "PGND") (class "Default")
      (node (ref "C18") (pin "1") (pinfunction "1_1") (pintype "passive"))
      (node (ref "C3") (pin "2") (pinfunction "2_2") (pintype "passive"))
      (node (ref "C6") (pin "2") (pinfunction "2_2") (pintype "passive"))
      (node (ref "D1") (pin "2") (pinfunction "K_2") (pintype "passive"))
      (node (ref "D3") (pin "1") (pinfunction "A_1") (pintype "passive"))
      (node (ref "P1") (pin "3") (pinfunction "3_3") (pintype "passive"))
      (node (ref "P11") (pin "3") (pinfunction "3_3") (pintype "passive"))
      (node (ref "P12") (pin "3") (pinfunction "3_3") (pintype "passive"))
      (node (ref "P13") (pin "2") (pinfunction "2_2") (pintype "passive"))
      (node (ref "P2") (pin "2") (pinfunction "2_2") (pintype "passive"))
      (node (ref "P4") (pin "7") (pinfunction "7_7") (pintype "passive"))
      (node (ref "Q1") (pin "3") (pinfunction "S_3") (pintype "passive"))
      (node (ref "Q3") (pin "3") (pinfunction "S_3") (pintype "passive"))
      (node (ref "Q5") (pin "2") (pinfunction "E_2") (pintype "passive"))
      (node (ref "Q6") (pin "3") (pinfunction "S_3") (pintype "passive"))
      (node (ref "Q8") (pin "3") (pinfunction "S_3") (pintype "passive"))
      (node (ref "R1") (pin "1") (pinfunction "1_1") (pintype "passive"))
      (node (ref "R36") (pin "1") (pinfunction "1_1") (pintype "passive"))
      (node (ref "R4") (pin "2") (pinfunction "2_2") (pintype "passive"))
      (node (ref "R40") (pin "1") (pinfunction "1_1") (pintype "passive"))
      (node (ref "U1") (pin "5") (pinfunction "H_5") (pintype "passive"))
      (node (ref "U2") (pin "3") (pinfunction "GND_3") (pintype "power_in"))
      (node (ref "U2") (pin "5") (pinfunction "~{ON}/OFF_5") (pintype "input"))
      (node (ref "U8") (pin "4") (pinfunction "GND_4") (pintype "power_in"))
      (node (ref "U9") (pin "5") (pinfunction "GND_5") (pintype "passive"))
    )
    (net (code "86") (name "SGND") (class "Default")
      (node (ref "C10") (pin "1") (pinfunction "1_1") (pintype "passive"))
      (node (ref "C14") (pin "2") (pinfunction "2_2") (pintype "passive"))
      (node (ref "C15") (pin "2") (pinfunction "2_2") (pintype "passive"))
      (node (ref "C19") (pin "2") (pinfunction "2_2") (pintype "passive"))
      (node (ref "C20") (pin "2") (pinfunction "2_2") (pintype "passive"))
      (node (ref "C21") (pin "1") (pinfunction "1_1") (pintype "passive"))
      (node (ref "C22") (pin "2") (pinfunction "2_2") (pintype "passive"))
      (node (ref "C23") (pin "2") (pinfunction "2_2") (pintype "passive"))
      (node (ref "C4") (pin "2") (pinfunction "2_2") (pintype "passive"))
      (node (ref "C5") (pin "2") (pinfunction "2_2") (pintype "passive"))
      (node (ref "C8") (pin "2") (pinfunction "2_2") (pintype "passive"))
      (node (ref "C9") (pin "2") (pinfunction "2_2") (pintype "passive"))
      (node (ref "P10") (pin "4") (pinfunction "4_4") (pintype "passive"))
      (node (ref "P7") (pin "11") (pinfunction "GND_11") (pintype "passive"))
      (node (ref "P7") (pin "2") (pinfunction "GND_2") (pintype "passive"))
      (node (ref "P9") (pin "4") (pinfunction "4_4") (pintype "passive"))
      (node (ref "Q2") (pin "2") (pinfunction "E_2") (pintype "passive"))
      (node (ref "Q4") (pin "2") (pinfunction "E_2") (pintype "passive"))
      (node (ref "Q7") (pin "2") (pinfunction "E_2") (pintype "passive"))
      (node (ref "Q9") (pin "2") (pinfunction "E_2") (pintype "passive"))
      (node (ref "R1") (pin "2") (pinfunction "2_2") (pintype "passive"))
      (node (ref "R11") (pin "2") (pinfunction "2_2") (pintype "passive"))
      (node (ref "R24") (pin "1") (pinfunction "1_1") (pintype "passive"))
      (node (ref "R28") (pin "1") (pinfunction "A0_1") (pintype "passive"))
      (node (ref "R28") (pin "2") (pinfunction "A1_2") (pintype "passive"))
      (node (ref "R28") (pin "3") (pinfunction "A2_3") (pintype "passive"))
      (node (ref "R28") (pin "4") (pinfunction "GND_4") (pintype "passive"))
      (node (ref "R28") (pin "7") (pinfunction "WP_7") (pintype "passive"))
      (node (ref "R31") (pin "1") (pinfunction "1_1") (pintype "passive"))
      (node (ref "R37") (pin "1") (pinfunction "1_1") (pintype "passive"))
      (node (ref "S1") (pin "1") (pinfunction "A1_1") (pintype "passive"))
      (node (ref "S1") (pin "2") (pinfunction "A2_2") (pintype "passive"))
      (node (ref "S2") (pin "1") (pinfunction "1_1") (pintype "passive"))
      (node (ref "U3") (pin "9") (pinfunction "GND_9") (pintype "passive"))
      (node (ref "U4") (pin "1") (pinfunction "Ground_1") (pintype "passive"))
      (node (ref "U5") (pin "10") (pinfunction "GND_10") (pintype "passive"))
      (node (ref "U5") (pin "12") (pinfunction "GND_12") (pintype "passive"))
      (node (ref "U5") (pin "5") (pinfunction "GND_5") (pintype "passive"))
      (node (ref "U6") (pin "12") (pinfunction "VSSA_12") (pintype "power_in"))
      (node (ref "U6") (pin "18") (pinfunction "VSS_4_18") (pintype "power_in"))
      (node (ref "U6") (pin "31") (pinfunction "VSS_1_31") (pintype "power_in"))
      (node (ref "U6") (pin "47") (pinfunction "VSS_2_47") (pintype "power_in"))
      (node (ref "U6") (pin "63") (pinfunction "VSS_3_63") (pintype "power_in"))
      (node (ref "U7") (pin "1") (pinfunction "GND_1") (pintype "passive"))
    )
    (net (code "87") (name "unconnected-(P7-ANT-Pad1)") (class "Default")
      (node (ref "P7") (pin "1") (pinfunction "ANT_1") (pintype "passive+no_connect"))
    )
    (net (code "88") (name "unconnected-(P7-D3-Pad9)") (class "Default")
      (node (ref "P7") (pin "9") (pinfunction "D3_9") (pintype "passive+no_connect"))
    )
    (net (code "89") (name "unconnected-(U1-A-Pad3)") (class "Default")
      (node (ref "U1") (pin "3") (pinfunction "A_3") (pintype "passive+no_connect"))
    )
    (net (code "90") (name "unconnected-(U1-B-Pad4)") (class "Default")
      (node (ref "U1") (pin "4") (pinfunction "B_4") (pintype "passive+no_connect"))
    )
    (net (code "91") (name "unconnected-(U2-TAB-Pad6)") (class "Default")
      (node (ref "U2") (pin "6") (pinfunction "TAB_6") (pintype "power_in+no_connect"))
    )
    (net (code "92") (name "unconnected-(U3-ADC-Pad2)") (class "Default")
      (node (ref "U3") (pin "2") (pinfunction "ADC_2") (pintype "passive+no_connect"))
    )
    (net (code "93") (name "unconnected-(U3-GPIO0-Pad12)") (class "Default")
      (node (ref "U3") (pin "12") (pinfunction "GPIO0_12") (pintype "passive+no_connect"))
    )
    (net (code "94") (name "unconnected-(U3-GPIO2-Pad11)") (class "Default")
      (node (ref "U3") (pin "11") (pinfunction "GPIO2_11") (pintype "passive+no_connect"))
    )
    (net (code "95") (name "unconnected-(U3-GPIO4-Pad14)") (class "Default")
      (node (ref "U3") (pin "14") (pinfunction "GPIO4_14") (pintype "passive+no_connect"))
    )
    (net (code "96") (name "unconnected-(U3-GPIO5-Pad13)") (class "Default")
      (node (ref "U3") (pin "13") (pinfunction "GPIO5_13") (pintype "passive+no_connect"))
    )
    (net (code "97") (name "unconnected-(U3-GPIO12-Pad6)") (class "Default")
      (node (ref "U3") (pin "6") (pinfunction "GPIO12_6") (pintype "passive+no_connect"))
    )
    (net (code "98") (name "unconnected-(U3-GPIO13-Pad7)") (class "Default")
      (node (ref "U3") (pin "7") (pinfunction "GPIO13_7") (pintype "passive+no_connect"))
    )
    (net (code "99") (name "unconnected-(U3-GPIO14-Pad5)") (class "Default")
      (node (ref "U3") (pin "5") (pinfunction "GPIO14_5") (pintype "passive+no_connect"))
    )
    (net (code "100") (name "unconnected-(U3-GPIO16-Pad4)") (class "Default")
      (node (ref "U3") (pin "4") (pinfunction "GPIO16_4") (pintype "passive+no_connect"))
    )
    (net (code "101") (name "unconnected-(U5-INT1-Pad11)") (class "Default")
      (node (ref "U5") (pin "11") (pinfunction "INT1_11") (pintype "passive+no_connect"))
    )
    (net (code "102") (name "unconnected-(U5-INT2-Pad9)") (class "Default")
      (node (ref "U5") (pin "9") (pinfunction "INT2_9") (pintype "passive+no_connect"))
    )
    (net (code "103") (name "unconnected-(U5-NC-Pad3)") (class "Default")
      (node (ref "U5") (pin "3") (pinfunction "NC_3") (pintype "passive"))
    )
    (net (code "104") (name "unconnected-(U5-NC-Pad8)") (class "Default")
      (node (ref "U5") (pin "8") (pinfunction "NC_8") (pintype "passive"))
    )
    (net (code "105") (name "unconnected-(U5-NC-Pad13)") (class "Default")
      (node (ref "U5") (pin "13") (pinfunction "NC_13") (pintype "passive"))
    )
    (net (code "106") (name "unconnected-(U5-NC-Pad15)") (class "Default")
      (node (ref "U5") (pin "15") (pinfunction "NC_15") (pintype "passive"))
    )
    (net (code "107") (name "unconnected-(U5-NC-Pad16)") (class "Default")
      (node (ref "U5") (pin "16") (pinfunction "NC_16") (pintype "passive"))
    )
    (net (code "108") (name "unconnected-(U6A-PB8-Pad61)") (class "Default")
      (node (ref "U6") (pin "61") (pinfunction "PB8_61") (pintype "bidirectional+no_connect"))
    )
    (net (code "109") (name "unconnected-(U6A-PB9-Pad62)") (class "Default")
      (node (ref "U6") (pin "62") (pinfunction "PB9_62") (pintype "bidirectional+no_connect"))
    )
    (net (code "110") (name "unconnected-(U6A-PC1-Pad9)") (class "Default")
      (node (ref "U6") (pin "9") (pinfunction "PC1_9") (pintype "bidirectional+no_connect"))
    )
    (net (code "111") (name "unconnected-(U6A-PC4-Pad24)") (class "Default")
      (node (ref "U6") (pin "24") (pinfunction "PC4_24") (pintype "bidirectional+no_connect"))
    )
    (net (code "112") (name "unconnected-(U6A-PC5-Pad25)") (class "Default")
      (node (ref "U6") (pin "25") (pinfunction "PC5_25") (pintype "bidirectional+no_connect"))
    )
    (net (code "113") (name "unconnected-(U6A-PC7-Pad38)") (class "Default")
      (node (ref "U6") (pin "38") (pinfunction "PC7_38") (pintype "bidirectional"))
    )
    (net (code "114") (name "unconnected-(U6A-PC9-Pad40)") (class "Default")
      (node (ref "U6") (pin "40") (pinfunction "PC9_40") (pintype "bidirectional+no_connect"))
    )
    (net (code "115") (name "unconnected-(U6B-VBAT-Pad1)") (class "Default")
      (node (ref "U6") (pin "1") (pinfunction "VBAT_1") (pintype "power_in+no_connect"))
    )
  )
)
